# Curtis3340-VCO.net
KiCad netlist of a schematic drawn in EAGLE
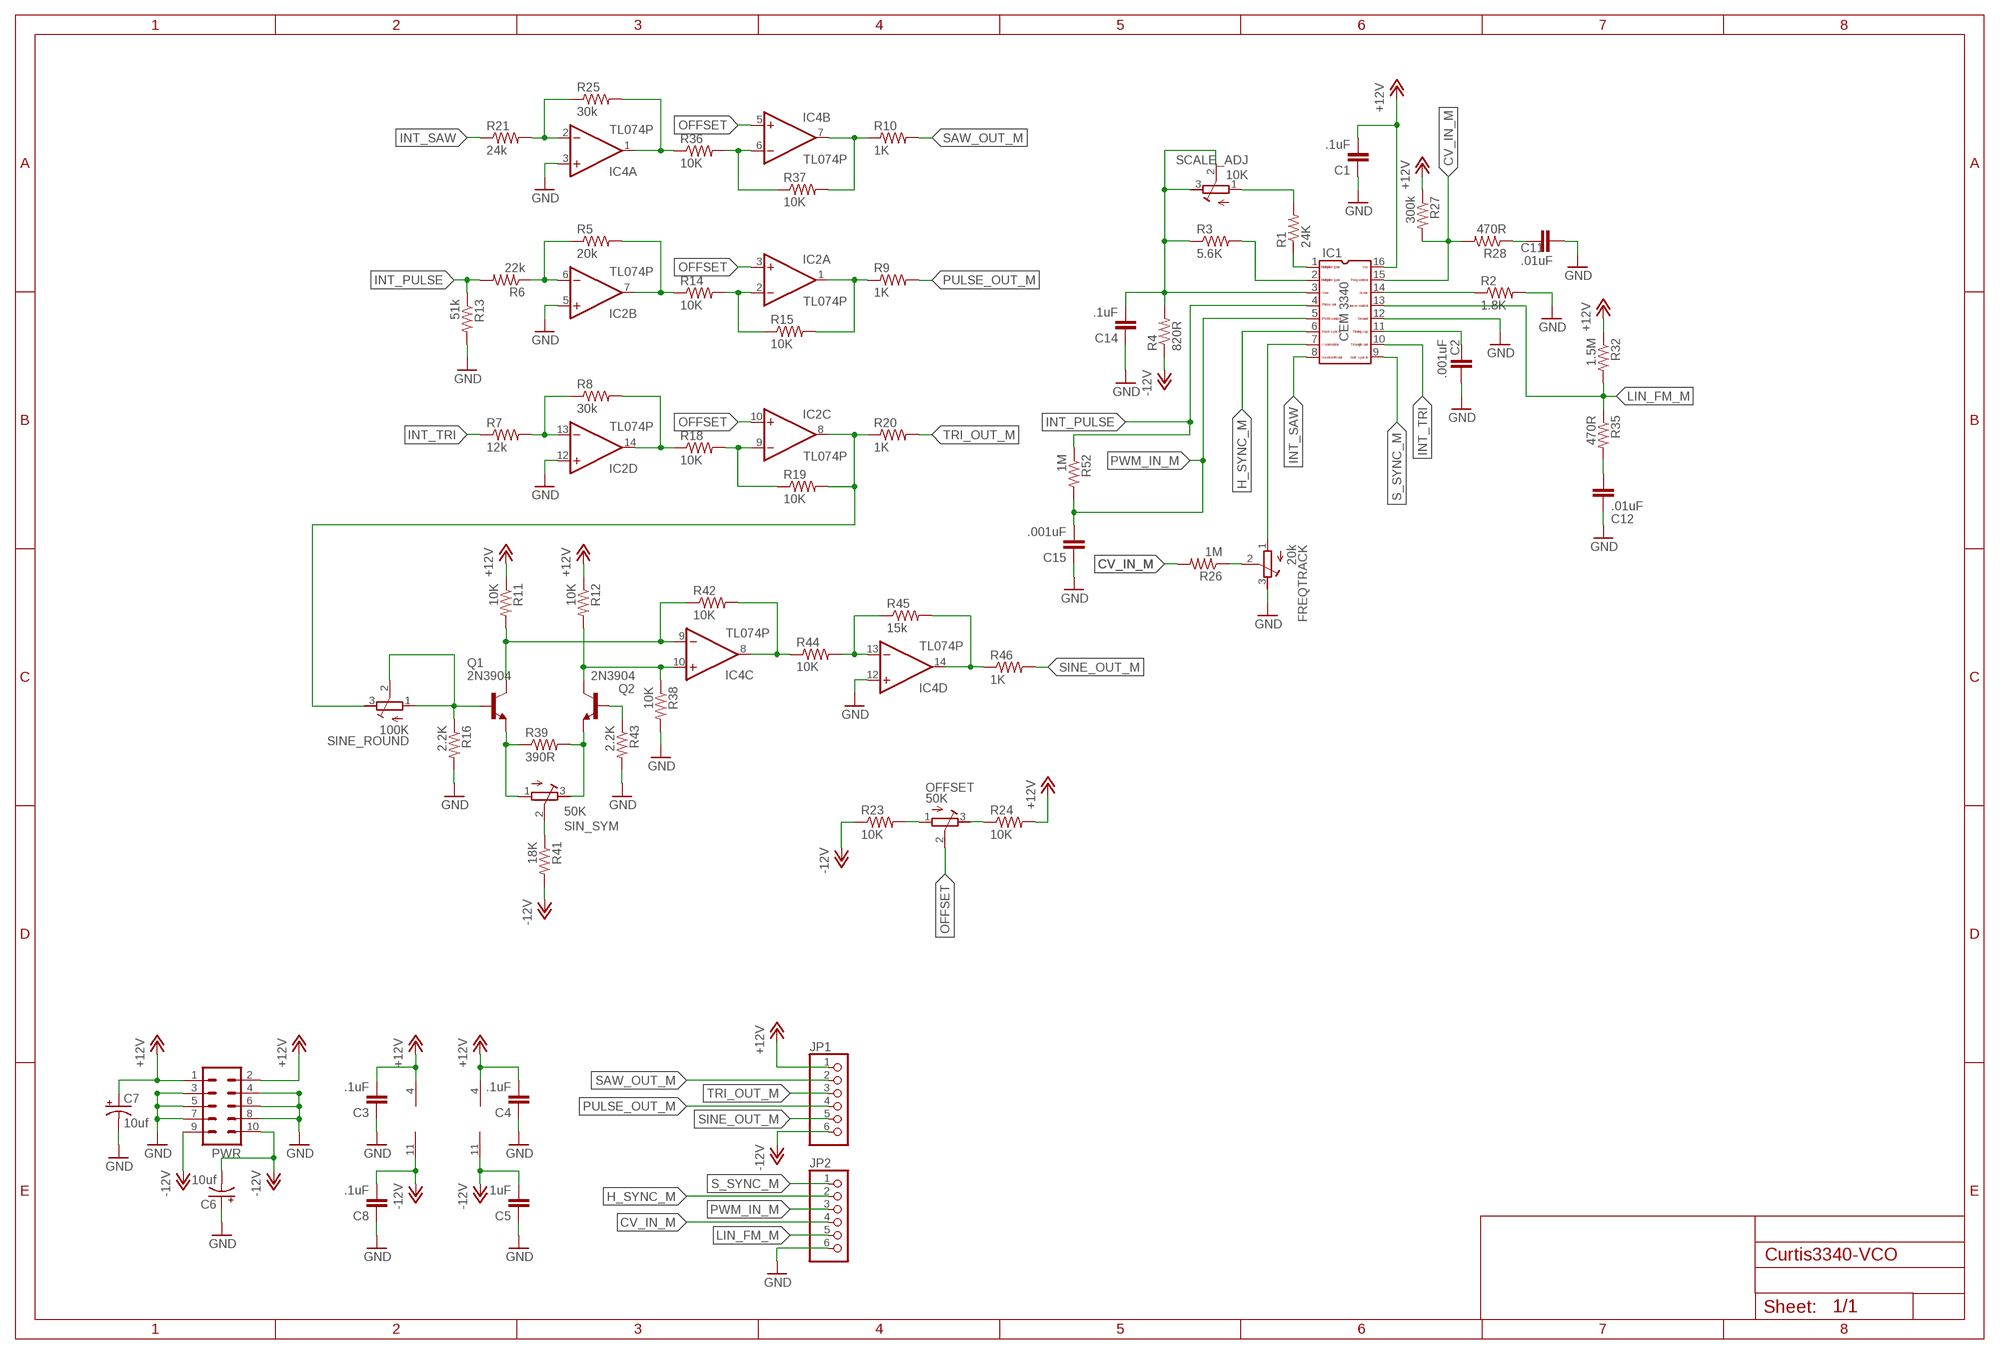
[diagram p0: schematic, sheet 1]

(export (version "E")
  (design (tool "Eeschema 10.0.6"))
  (components
    (comp (ref "C1")
      (value ".1uF")
      (footprint "eagle-import:C050-024X044")
      (libsource (lib "eagle-import") (part "resistor_C-EU050-024X044"))
    )
    (comp (ref "C2")
      (value ".001uF")
      (footprint "eagle-import:C150-054X183")
      (libsource (lib "eagle-import") (part "C-EU150-054X183"))
    )
    (comp (ref "C3")
      (value ".1uF")
      (footprint "eagle-import:C050-024X044")
      (libsource (lib "eagle-import") (part "resistor_C-EU050-024X044"))
    )
    (comp (ref "C4")
      (value ".1uF")
      (footprint "eagle-import:C050-024X044")
      (libsource (lib "eagle-import") (part "resistor_C-EU050-024X044"))
    )
    (comp (ref "C5")
      (value ".1uF")
      (footprint "eagle-import:C050-024X044")
      (libsource (lib "eagle-import") (part "resistor_C-EU050-024X044"))
    )
    (comp (ref "C6")
      (value "10uf")
      (footprint "eagle-import:E2,5-5")
      (libsource (lib "eagle-import") (part "CPOL-USE2.5-5"))
    )
    (comp (ref "C7")
      (value "10uf")
      (footprint "eagle-import:E2,5-5")
      (libsource (lib "eagle-import") (part "CPOL-USE2.5-5"))
    )
    (comp (ref "C8")
      (value ".1uF")
      (footprint "eagle-import:C050-024X044")
      (libsource (lib "eagle-import") (part "resistor_C-EU050-024X044"))
    )
    (comp (ref "C11")
      (value ".01uF")
      (footprint "eagle-import:C050-024X044")
      (libsource (lib "eagle-import") (part "resistor_C-EU050-024X044"))
    )
    (comp (ref "C12")
      (value ".01uF")
      (footprint "eagle-import:C050-024X044")
      (libsource (lib "eagle-import") (part "resistor_C-EU050-024X044"))
    )
    (comp (ref "C14")
      (value ".1uF")
      (footprint "eagle-import:C050-024X044")
      (libsource (lib "eagle-import") (part "resistor_C-EU050-024X044"))
    )
    (comp (ref "C15")
      (value ".001uF")
      (footprint "eagle-import:C050-024X044")
      (libsource (lib "eagle-import") (part "resistor_C-EU050-024X044"))
    )
    (comp (ref "FREQTRACK")
      (value "20k")
      (footprint "eagle-import:RTRIM3296W")
      (libsource (lib "eagle-import") (part "R-TRIMM3296W"))
    )
    (comp (ref "IC1")
      (value "CEM3340")
      (footprint "eagle-import:DIL16")
      (libsource (lib "eagle-import") (part "CEM3340"))
    )
    (comp (ref "IC2")
      (value "TL074P")
      (footprint "eagle-import:DIL14")
      (libsource (lib "eagle-import") (part "TL074P"))
    )
    (comp (ref "IC4")
      (value "TL074P")
      (footprint "eagle-import:DIL14")
      (libsource (lib "eagle-import") (part "linear_262_TL074P"))
    )
    (comp (ref "JP1")
      (value "PINHD-1X6")
      (footprint "eagle-import:1X06")
      (libsource (lib "eagle-import") (part "PINHD-1X6"))
    )
    (comp (ref "JP2")
      (value "PINHD-1X6")
      (footprint "eagle-import:1X06")
      (libsource (lib "eagle-import") (part "PINHD-1X6"))
    )
    (comp (ref "OFFSET")
      (value "50K")
      (footprint "eagle-import:RTRIM3296W")
      (libsource (lib "eagle-import") (part "R-TRIMM3296W"))
    )
    (comp (ref "PWR")
      (value "ML10")
      (footprint "eagle-import:ML10")
      (libsource (lib "eagle-import") (part "ML10"))
    )
    (comp (ref "Q1")
      (value "2N3904")
      (footprint "eagle-import:TO92")
      (libsource (lib "eagle-import") (part "2N3904"))
    )
    (comp (ref "Q2")
      (value "2N3904")
      (footprint "eagle-import:TO92")
      (libsource (lib "eagle-import") (part "2N3904"))
    )
    (comp (ref "R1")
      (value "24K")
      (footprint "eagle-import:0207_7")
      (libsource (lib "eagle-import") (part "R-US_0207/7"))
    )
    (comp (ref "R2")
      (value "1.8K")
      (footprint "eagle-import:0207_7")
      (libsource (lib "eagle-import") (part "R-US_0207/7"))
    )
    (comp (ref "R3")
      (value "5.6K")
      (footprint "eagle-import:0207_7")
      (libsource (lib "eagle-import") (part "R-US_0207/7"))
    )
    (comp (ref "R4")
      (value "820R")
      (footprint "eagle-import:0207_7")
      (libsource (lib "eagle-import") (part "R-US_0207/7"))
    )
    (comp (ref "R5")
      (value "20k")
      (footprint "eagle-import:0207_7")
      (libsource (lib "eagle-import") (part "R-US_0207/7"))
    )
    (comp (ref "R6")
      (value "22k")
      (footprint "eagle-import:0207_7")
      (libsource (lib "eagle-import") (part "R-US_0207/7"))
    )
    (comp (ref "R7")
      (value "12k")
      (footprint "eagle-import:0207_7")
      (libsource (lib "eagle-import") (part "R-US_0207/7"))
    )
    (comp (ref "R8")
      (value "30k")
      (footprint "eagle-import:0207_7")
      (libsource (lib "eagle-import") (part "R-US_0207/7"))
    )
    (comp (ref "R9")
      (value "1K")
      (footprint "eagle-import:0207_7")
      (libsource (lib "eagle-import") (part "R-US_0207/7"))
    )
    (comp (ref "R10")
      (value "1K")
      (footprint "eagle-import:0207_7")
      (libsource (lib "eagle-import") (part "R-US_0207/7"))
    )
    (comp (ref "R11")
      (value "10K")
      (footprint "eagle-import:0207_7")
      (libsource (lib "eagle-import") (part "R-US_0207/7"))
    )
    (comp (ref "R12")
      (value "10K")
      (footprint "eagle-import:0207_7")
      (libsource (lib "eagle-import") (part "R-US_0207/7"))
    )
    (comp (ref "R13")
      (value "51k")
      (footprint "eagle-import:0207_7")
      (libsource (lib "eagle-import") (part "R-US_0207/7"))
    )
    (comp (ref "R14")
      (value "10K")
      (footprint "eagle-import:0207_7")
      (libsource (lib "eagle-import") (part "R-US_0207/7"))
    )
    (comp (ref "R15")
      (value "10K")
      (footprint "eagle-import:0207_7")
      (libsource (lib "eagle-import") (part "R-US_0207/7"))
    )
    (comp (ref "R16")
      (value "2.2K")
      (footprint "eagle-import:0207_7")
      (libsource (lib "eagle-import") (part "R-US_0207/7"))
    )
    (comp (ref "R18")
      (value "10K")
      (footprint "eagle-import:0207_7")
      (libsource (lib "eagle-import") (part "R-US_0207/7"))
    )
    (comp (ref "R19")
      (value "10K")
      (footprint "eagle-import:0207_7")
      (libsource (lib "eagle-import") (part "R-US_0207/7"))
    )
    (comp (ref "R20")
      (value "1K")
      (footprint "eagle-import:0207_7")
      (libsource (lib "eagle-import") (part "R-US_0207/7"))
    )
    (comp (ref "R21")
      (value "24k")
      (footprint "eagle-import:0207_7")
      (libsource (lib "eagle-import") (part "R-US_0207/7"))
    )
    (comp (ref "R23")
      (value "10K")
      (footprint "eagle-import:0207_7")
      (libsource (lib "eagle-import") (part "R-US_0207/7"))
    )
    (comp (ref "R24")
      (value "10K")
      (footprint "eagle-import:0207_7")
      (libsource (lib "eagle-import") (part "resistor_348_R-US_0207/7"))
    )
    (comp (ref "R25")
      (value "30k")
      (footprint "eagle-import:0207_7")
      (libsource (lib "eagle-import") (part "R-US_0207/7"))
    )
    (comp (ref "R26")
      (value "1M")
      (footprint "eagle-import:0207_7")
      (libsource (lib "eagle-import") (part "R-US_0207/7"))
    )
    (comp (ref "R27")
      (value "300k")
      (footprint "eagle-import:0207_7")
      (libsource (lib "eagle-import") (part "R-US_0207/7"))
    )
    (comp (ref "R28")
      (value "470R")
      (footprint "eagle-import:0207_7")
      (libsource (lib "eagle-import") (part "R-US_0207/7"))
    )
    (comp (ref "R32")
      (value "1.5M")
      (footprint "eagle-import:0207_7")
      (libsource (lib "eagle-import") (part "R-US_0207/7"))
    )
    (comp (ref "R35")
      (value "470R")
      (footprint "eagle-import:0207_7")
      (libsource (lib "eagle-import") (part "R-US_0207/7"))
    )
    (comp (ref "R36")
      (value "10K")
      (footprint "eagle-import:0207_7")
      (libsource (lib "eagle-import") (part "R-US_0207/7"))
    )
    (comp (ref "R37")
      (value "10K")
      (footprint "eagle-import:0207_7")
      (libsource (lib "eagle-import") (part "R-US_0207/7"))
    )
    (comp (ref "R38")
      (value "10K")
      (footprint "eagle-import:0207_7")
      (libsource (lib "eagle-import") (part "R-US_0207/7"))
    )
    (comp (ref "R39")
      (value "390R")
      (footprint "eagle-import:0207_7")
      (libsource (lib "eagle-import") (part "R-US_0207/7"))
    )
    (comp (ref "R41")
      (value "18K")
      (footprint "eagle-import:0207_7")
      (libsource (lib "eagle-import") (part "R-US_0207/7"))
    )
    (comp (ref "R42")
      (value "10K")
      (footprint "eagle-import:0207_7")
      (libsource (lib "eagle-import") (part "R-US_0207/7"))
    )
    (comp (ref "R43")
      (value "2.2K")
      (footprint "eagle-import:0207_7")
      (libsource (lib "eagle-import") (part "R-US_0207/7"))
    )
    (comp (ref "R44")
      (value "10K")
      (footprint "eagle-import:0207_7")
      (libsource (lib "eagle-import") (part "R-US_0207/7"))
    )
    (comp (ref "R45")
      (value "15k")
      (footprint "eagle-import:0207_7")
      (libsource (lib "eagle-import") (part "R-US_0207/7"))
    )
    (comp (ref "R46")
      (value "1K")
      (footprint "eagle-import:0207_7")
      (libsource (lib "eagle-import") (part "R-US_0207/7"))
    )
    (comp (ref "R52")
      (value "1M")
      (footprint "eagle-import:0207_7")
      (libsource (lib "eagle-import") (part "R-US_0207/7"))
    )
    (comp (ref "SCALE_ADJ")
      (value "10K")
      (footprint "eagle-import:RTRIM3296W")
      (libsource (lib "eagle-import") (part "R-TRIMM3296W"))
    )
    (comp (ref "SINE_ROUND")
      (value "100K")
      (footprint "eagle-import:RTRIM3296W")
      (libsource (lib "eagle-import") (part "R-TRIMM3296W"))
    )
    (comp (ref "SIN_SYM")
      (value "50K")
      (footprint "eagle-import:RTRIM3296W")
      (libsource (lib "eagle-import") (part "R-TRIMM3296W"))
    )
  )
  (nets
    (net (code "1") (name "+12V") (class "Default")
      (node (ref "C1") (pin "2") (pinfunction "2_2") (pintype "passive"))
      (node (ref "C3") (pin "2") (pinfunction "2_2") (pintype "passive"))
      (node (ref "C4") (pin "2") (pinfunction "2_2") (pintype "passive"))
      (node (ref "C7") (pin "+") (pinfunction "+_+") (pintype "passive"))
      (node (ref "IC1") (pin "16") (pinfunction "16_16") (pintype "power_in"))
      (node (ref "IC2") (pin "4") (pinfunction "V+_4") (pintype "power_in"))
      (node (ref "IC4") (pin "4") (pinfunction "V+_4") (pintype "power_in"))
      (node (ref "JP1") (pin "1") (pinfunction "1_1") (pintype "passive"))
      (node (ref "PWR") (pin "1") (pinfunction "1_1") (pintype "passive"))
      (node (ref "PWR") (pin "2") (pinfunction "2_2") (pintype "passive"))
      (node (ref "R11") (pin "1") (pinfunction "1_1") (pintype "passive"))
      (node (ref "R12") (pin "1") (pinfunction "1_1") (pintype "passive"))
      (node (ref "R24") (pin "2") (pinfunction "2_2") (pintype "passive"))
      (node (ref "R27") (pin "1") (pinfunction "1_1") (pintype "passive"))
      (node (ref "R32") (pin "1") (pinfunction "1_1") (pintype "passive"))
    )
    (net (code "2") (name "-12V") (class "Default")
      (node (ref "C5") (pin "2") (pinfunction "2_2") (pintype "passive"))
      (node (ref "C6") (pin "-") (pinfunction "-_-") (pintype "passive"))
      (node (ref "C8") (pin "2") (pinfunction "2_2") (pintype "passive"))
      (node (ref "IC2") (pin "11") (pinfunction "V-_11") (pintype "power_in"))
      (node (ref "IC4") (pin "11") (pinfunction "V-_11") (pintype "power_in"))
      (node (ref "JP1") (pin "6") (pinfunction "6_6") (pintype "passive"))
      (node (ref "PWR") (pin "10") (pinfunction "10_10") (pintype "passive"))
      (node (ref "PWR") (pin "9") (pinfunction "9_9") (pintype "passive"))
      (node (ref "R23") (pin "1") (pinfunction "1_1") (pintype "passive"))
      (node (ref "R4") (pin "1") (pinfunction "1_1") (pintype "passive"))
      (node (ref "R41") (pin "2") (pinfunction "2_2") (pintype "passive"))
    )
    (net (code "3") (name "CV_IN_M") (class "Default")
      (node (ref "IC1") (pin "15") (pinfunction "15_15") (pintype "input"))
      (node (ref "JP2") (pin "4") (pinfunction "4_4") (pintype "passive"))
      (node (ref "R26") (pin "2") (pinfunction "2_2") (pintype "passive"))
      (node (ref "R27") (pin "2") (pinfunction "2_2") (pintype "passive"))
      (node (ref "R28") (pin "2") (pinfunction "2_2") (pintype "passive"))
    )
    (net (code "4") (name "GND") (class "Default")
      (node (ref "C1") (pin "1") (pinfunction "1_1") (pintype "passive"))
      (node (ref "C11") (pin "1") (pinfunction "1_1") (pintype "passive"))
      (node (ref "C12") (pin "2") (pinfunction "2_2") (pintype "passive"))
      (node (ref "C14") (pin "1") (pinfunction "1_1") (pintype "passive"))
      (node (ref "C15") (pin "1") (pinfunction "1_1") (pintype "passive"))
      (node (ref "C2") (pin "2") (pinfunction "2_2") (pintype "passive"))
      (node (ref "C3") (pin "1") (pinfunction "1_1") (pintype "passive"))
      (node (ref "C4") (pin "1") (pinfunction "1_1") (pintype "passive"))
      (node (ref "C5") (pin "1") (pinfunction "1_1") (pintype "passive"))
      (node (ref "C6") (pin "+") (pinfunction "+_+") (pintype "passive"))
      (node (ref "C7") (pin "-") (pinfunction "-_-") (pintype "passive"))
      (node (ref "C8") (pin "1") (pinfunction "1_1") (pintype "passive"))
      (node (ref "FREQTRACK") (pin "3") (pinfunction "E_3") (pintype "passive"))
      (node (ref "IC1") (pin "12") (pinfunction "12_12") (pintype "power_in"))
      (node (ref "IC2") (pin "12") (pinfunction "+IN_12") (pintype "input"))
      (node (ref "IC2") (pin "5") (pinfunction "+IN_5") (pintype "input"))
      (node (ref "IC4") (pin "12") (pinfunction "+IN_12") (pintype "input"))
      (node (ref "IC4") (pin "3") (pinfunction "+IN_3") (pintype "input"))
      (node (ref "JP2") (pin "6") (pinfunction "6_6") (pintype "passive"))
      (node (ref "PWR") (pin "3") (pinfunction "3_3") (pintype "passive"))
      (node (ref "PWR") (pin "4") (pinfunction "4_4") (pintype "passive"))
      (node (ref "PWR") (pin "5") (pinfunction "5_5") (pintype "passive"))
      (node (ref "PWR") (pin "6") (pinfunction "6_6") (pintype "passive"))
      (node (ref "PWR") (pin "7") (pinfunction "7_7") (pintype "passive"))
      (node (ref "PWR") (pin "8") (pinfunction "8_8") (pintype "passive"))
      (node (ref "R13") (pin "2") (pinfunction "2_2") (pintype "passive"))
      (node (ref "R16") (pin "2") (pinfunction "2_2") (pintype "passive"))
      (node (ref "R2") (pin "2") (pinfunction "2_2") (pintype "passive"))
      (node (ref "R38") (pin "2") (pinfunction "2_2") (pintype "passive"))
      (node (ref "R43") (pin "2") (pinfunction "2_2") (pintype "passive"))
    )
    (net (code "5") (name "H_SYNC_M") (class "Default")
      (node (ref "IC1") (pin "6") (pinfunction "6_6") (pintype "input"))
      (node (ref "JP2") (pin "2") (pinfunction "2_2") (pintype "passive"))
    )
    (net (code "6") (name "INT_PULSE") (class "Default")
      (node (ref "IC1") (pin "4") (pinfunction "4_4") (pintype "output"))
      (node (ref "R13") (pin "1") (pinfunction "1_1") (pintype "passive"))
      (node (ref "R52") (pin "1") (pinfunction "1_1") (pintype "passive"))
      (node (ref "R6") (pin "2") (pinfunction "2_2") (pintype "passive"))
    )
    (net (code "7") (name "INT_SAW") (class "Default")
      (node (ref "IC1") (pin "8") (pinfunction "8_8") (pintype "output"))
      (node (ref "R21") (pin "1") (pinfunction "1_1") (pintype "passive"))
    )
    (net (code "8") (name "INT_TRI") (class "Default")
      (node (ref "IC1") (pin "10") (pinfunction "10_10") (pintype "output"))
      (node (ref "R7") (pin "1") (pinfunction "1_1") (pintype "passive"))
    )
    (net (code "9") (name "LIN_FM_M") (class "Default")
      (node (ref "IC1") (pin "13") (pinfunction "13_13") (pintype "input"))
      (node (ref "JP2") (pin "5") (pinfunction "5_5") (pintype "passive"))
      (node (ref "R32") (pin "2") (pinfunction "2_2") (pintype "passive"))
      (node (ref "R35") (pin "1") (pinfunction "1_1") (pintype "passive"))
    )
    (net (code "10") (name "Net-(C2-Pad1)") (class "Default")
      (node (ref "C2") (pin "1") (pinfunction "1_1") (pintype "passive"))
      (node (ref "IC1") (pin "11") (pinfunction "11_11") (pintype "bidirectional"))
    )
    (net (code "11") (name "Net-(C11-Pad2)") (class "Default")
      (node (ref "C11") (pin "2") (pinfunction "2_2") (pintype "passive"))
      (node (ref "R28") (pin "1") (pinfunction "1_1") (pintype "passive"))
    )
    (net (code "12") (name "Net-(C12-Pad1)") (class "Default")
      (node (ref "C12") (pin "1") (pinfunction "1_1") (pintype "passive"))
      (node (ref "R35") (pin "2") (pinfunction "2_2") (pintype "passive"))
    )
    (net (code "13") (name "Net-(FREQTRACK-A)") (class "Default")
      (node (ref "FREQTRACK") (pin "1") (pinfunction "A_1") (pintype "passive"))
      (node (ref "IC1") (pin "7") (pinfunction "7_7") (pintype "bidirectional"))
    )
    (net (code "14") (name "Net-(FREQTRACK-S)") (class "Default")
      (node (ref "FREQTRACK") (pin "2") (pinfunction "S_2") (pintype "passive"))
      (node (ref "R26") (pin "1") (pinfunction "1_1") (pintype "passive"))
    )
    (net (code "15") (name "Net-(IC1-Pad1)") (class "Default")
      (node (ref "IC1") (pin "1") (pinfunction "1_1") (pintype "bidirectional"))
      (node (ref "R1") (pin "1") (pinfunction "1_1") (pintype "passive"))
    )
    (net (code "16") (name "Net-(IC1-Pad2)") (class "Default")
      (node (ref "IC1") (pin "2") (pinfunction "2_2") (pintype "bidirectional"))
      (node (ref "R3") (pin "2") (pinfunction "2_2") (pintype "passive"))
    )
    (net (code "17") (name "Net-(IC1-Pad14)") (class "Default")
      (node (ref "IC1") (pin "14") (pinfunction "14_14") (pintype "input"))
      (node (ref "R2") (pin "1") (pinfunction "1_1") (pintype "passive"))
    )
    (net (code "18") (name "Net-(IC2A--IN)") (class "Default")
      (node (ref "IC2") (pin "2") (pinfunction "-IN_2") (pintype "input"))
      (node (ref "R14") (pin "2") (pinfunction "2_2") (pintype "passive"))
      (node (ref "R15") (pin "1") (pinfunction "1_1") (pintype "passive"))
    )
    (net (code "19") (name "Net-(IC2A-OUT)") (class "Default")
      (node (ref "IC2") (pin "1") (pinfunction "OUT_1") (pintype "output"))
      (node (ref "R15") (pin "2") (pinfunction "2_2") (pintype "passive"))
      (node (ref "R9") (pin "1") (pinfunction "1_1") (pintype "passive"))
    )
    (net (code "20") (name "Net-(IC2B--IN)") (class "Default")
      (node (ref "IC2") (pin "6") (pinfunction "-IN_6") (pintype "input"))
      (node (ref "R5") (pin "1") (pinfunction "1_1") (pintype "passive"))
      (node (ref "R6") (pin "1") (pinfunction "1_1") (pintype "passive"))
    )
    (net (code "21") (name "Net-(IC2B-OUT)") (class "Default")
      (node (ref "IC2") (pin "7") (pinfunction "OUT_7") (pintype "output"))
      (node (ref "R14") (pin "1") (pinfunction "1_1") (pintype "passive"))
      (node (ref "R5") (pin "2") (pinfunction "2_2") (pintype "passive"))
    )
    (net (code "22") (name "Net-(IC2C--IN)") (class "Default")
      (node (ref "IC2") (pin "9") (pinfunction "-IN_9") (pintype "input"))
      (node (ref "R18") (pin "2") (pinfunction "2_2") (pintype "passive"))
      (node (ref "R19") (pin "1") (pinfunction "1_1") (pintype "passive"))
    )
    (net (code "23") (name "Net-(IC2C-OUT)") (class "Default")
      (node (ref "IC2") (pin "8") (pinfunction "OUT_8") (pintype "output"))
      (node (ref "R19") (pin "2") (pinfunction "2_2") (pintype "passive"))
      (node (ref "R20") (pin "1") (pinfunction "1_1") (pintype "passive"))
      (node (ref "SINE_ROUND") (pin "3") (pinfunction "E_3") (pintype "passive"))
    )
    (net (code "24") (name "Net-(IC2D--IN)") (class "Default")
      (node (ref "IC2") (pin "13") (pinfunction "-IN_13") (pintype "input"))
      (node (ref "R7") (pin "2") (pinfunction "2_2") (pintype "passive"))
      (node (ref "R8") (pin "1") (pinfunction "1_1") (pintype "passive"))
    )
    (net (code "25") (name "Net-(IC2D-OUT)") (class "Default")
      (node (ref "IC2") (pin "14") (pinfunction "OUT_14") (pintype "output"))
      (node (ref "R18") (pin "1") (pinfunction "1_1") (pintype "passive"))
      (node (ref "R8") (pin "2") (pinfunction "2_2") (pintype "passive"))
    )
    (net (code "26") (name "Net-(IC4A--IN)") (class "Default")
      (node (ref "IC4") (pin "2") (pinfunction "-IN_2") (pintype "input"))
      (node (ref "R21") (pin "2") (pinfunction "2_2") (pintype "passive"))
      (node (ref "R25") (pin "1") (pinfunction "1_1") (pintype "passive"))
    )
    (net (code "27") (name "Net-(IC4A-OUT)") (class "Default")
      (node (ref "IC4") (pin "1") (pinfunction "OUT_1") (pintype "output"))
      (node (ref "R25") (pin "2") (pinfunction "2_2") (pintype "passive"))
      (node (ref "R36") (pin "1") (pinfunction "1_1") (pintype "passive"))
    )
    (net (code "28") (name "Net-(IC4B--IN)") (class "Default")
      (node (ref "IC4") (pin "6") (pinfunction "-IN_6") (pintype "input"))
      (node (ref "R36") (pin "2") (pinfunction "2_2") (pintype "passive"))
      (node (ref "R37") (pin "1") (pinfunction "1_1") (pintype "passive"))
    )
    (net (code "29") (name "Net-(IC4B-OUT)") (class "Default")
      (node (ref "IC4") (pin "7") (pinfunction "OUT_7") (pintype "output"))
      (node (ref "R10") (pin "1") (pinfunction "1_1") (pintype "passive"))
      (node (ref "R37") (pin "2") (pinfunction "2_2") (pintype "passive"))
    )
    (net (code "30") (name "Net-(IC4C-+IN)") (class "Default")
      (node (ref "IC4") (pin "10") (pinfunction "+IN_10") (pintype "input"))
      (node (ref "Q2") (pin "1") (pinfunction "C_1") (pintype "passive"))
      (node (ref "R12") (pin "2") (pinfunction "2_2") (pintype "passive"))
      (node (ref "R38") (pin "1") (pinfunction "1_1") (pintype "passive"))
    )
    (net (code "31") (name "Net-(IC4C--IN)") (class "Default")
      (node (ref "IC4") (pin "9") (pinfunction "-IN_9") (pintype "input"))
      (node (ref "Q1") (pin "1") (pinfunction "C_1") (pintype "passive"))
      (node (ref "R11") (pin "2") (pinfunction "2_2") (pintype "passive"))
      (node (ref "R42") (pin "1") (pinfunction "1_1") (pintype "passive"))
    )
    (net (code "32") (name "Net-(IC4C-OUT)") (class "Default")
      (node (ref "IC4") (pin "8") (pinfunction "OUT_8") (pintype "output"))
      (node (ref "R42") (pin "2") (pinfunction "2_2") (pintype "passive"))
      (node (ref "R44") (pin "1") (pinfunction "1_1") (pintype "passive"))
    )
    (net (code "33") (name "Net-(IC4D--IN)") (class "Default")
      (node (ref "IC4") (pin "13") (pinfunction "-IN_13") (pintype "input"))
      (node (ref "R44") (pin "2") (pinfunction "2_2") (pintype "passive"))
      (node (ref "R45") (pin "1") (pinfunction "1_1") (pintype "passive"))
    )
    (net (code "34") (name "Net-(IC4D-OUT)") (class "Default")
      (node (ref "IC4") (pin "14") (pinfunction "OUT_14") (pintype "output"))
      (node (ref "R45") (pin "2") (pinfunction "2_2") (pintype "passive"))
      (node (ref "R46") (pin "1") (pinfunction "1_1") (pintype "passive"))
    )
    (net (code "35") (name "Net-(OFFSET-A)") (class "Default")
      (node (ref "OFFSET") (pin "1") (pinfunction "A_1") (pintype "passive"))
      (node (ref "R23") (pin "2") (pinfunction "2_2") (pintype "passive"))
    )
    (net (code "36") (name "Net-(OFFSET-E)") (class "Default")
      (node (ref "OFFSET") (pin "3") (pinfunction "E_3") (pintype "passive"))
      (node (ref "R24") (pin "1") (pinfunction "1_1") (pintype "passive"))
    )
    (net (code "37") (name "Net-(Q1-B)") (class "Default")
      (node (ref "Q1") (pin "2") (pinfunction "B_2") (pintype "passive"))
      (node (ref "R16") (pin "1") (pinfunction "1_1") (pintype "passive"))
      (node (ref "SINE_ROUND") (pin "1") (pinfunction "A_1") (pintype "passive"))
      (node (ref "SINE_ROUND") (pin "2") (pinfunction "S_2") (pintype "passive"))
    )
    (net (code "38") (name "Net-(Q1-E)") (class "Default")
      (node (ref "Q1") (pin "3") (pinfunction "E_3") (pintype "passive"))
      (node (ref "R39") (pin "1") (pinfunction "1_1") (pintype "passive"))
      (node (ref "SIN_SYM") (pin "1") (pinfunction "A_1") (pintype "passive"))
    )
    (net (code "39") (name "Net-(Q2-B)") (class "Default")
      (node (ref "Q2") (pin "2") (pinfunction "B_2") (pintype "passive"))
      (node (ref "R43") (pin "1") (pinfunction "1_1") (pintype "passive"))
    )
    (net (code "40") (name "Net-(Q2-E)") (class "Default")
      (node (ref "Q2") (pin "3") (pinfunction "E_3") (pintype "passive"))
      (node (ref "R39") (pin "2") (pinfunction "2_2") (pintype "passive"))
      (node (ref "SIN_SYM") (pin "3") (pinfunction "E_3") (pintype "passive"))
    )
    (net (code "41") (name "Net-(SCALE_ADJ-A)") (class "Default")
      (node (ref "R1") (pin "2") (pinfunction "2_2") (pintype "passive"))
      (node (ref "SCALE_ADJ") (pin "1") (pinfunction "A_1") (pintype "passive"))
    )
    (net (code "42") (name "Net-(SCALE_ADJ-E)") (class "Default")
      (node (ref "C14") (pin "2") (pinfunction "2_2") (pintype "passive"))
      (node (ref "IC1") (pin "3") (pinfunction "3_3") (pintype "power_in"))
      (node (ref "R3") (pin "1") (pinfunction "1_1") (pintype "passive"))
      (node (ref "R4") (pin "2") (pinfunction "2_2") (pintype "passive"))
      (node (ref "SCALE_ADJ") (pin "2") (pinfunction "S_2") (pintype "passive"))
      (node (ref "SCALE_ADJ") (pin "3") (pinfunction "E_3") (pintype "passive"))
    )
    (net (code "43") (name "Net-(SIN_SYM-S)") (class "Default")
      (node (ref "R41") (pin "1") (pinfunction "1_1") (pintype "passive"))
      (node (ref "SIN_SYM") (pin "2") (pinfunction "S_2") (pintype "passive"))
    )
    (net (code "44") (name "OFFSET") (class "Default")
      (node (ref "IC2") (pin "10") (pinfunction "+IN_10") (pintype "input"))
      (node (ref "IC2") (pin "3") (pinfunction "+IN_3") (pintype "input"))
      (node (ref "IC4") (pin "5") (pinfunction "+IN_5") (pintype "input"))
      (node (ref "OFFSET") (pin "2") (pinfunction "S_2") (pintype "passive"))
    )
    (net (code "45") (name "PULSE_OUT_M") (class "Default")
      (node (ref "JP1") (pin "4") (pinfunction "4_4") (pintype "passive"))
      (node (ref "R9") (pin "2") (pinfunction "2_2") (pintype "passive"))
    )
    (net (code "46") (name "PWM_IN_M") (class "Default")
      (node (ref "C15") (pin "2") (pinfunction "2_2") (pintype "passive"))
      (node (ref "IC1") (pin "5") (pinfunction "5_5") (pintype "input"))
      (node (ref "JP2") (pin "3") (pinfunction "3_3") (pintype "passive"))
      (node (ref "R52") (pin "2") (pinfunction "2_2") (pintype "passive"))
    )
    (net (code "47") (name "SAW_OUT_M") (class "Default")
      (node (ref "JP1") (pin "2") (pinfunction "2_2") (pintype "passive"))
      (node (ref "R10") (pin "2") (pinfunction "2_2") (pintype "passive"))
    )
    (net (code "48") (name "SINE_OUT_M") (class "Default")
      (node (ref "JP1") (pin "5") (pinfunction "5_5") (pintype "passive"))
      (node (ref "R46") (pin "2") (pinfunction "2_2") (pintype "passive"))
    )
    (net (code "49") (name "S_SYNC_M") (class "Default")
      (node (ref "IC1") (pin "9") (pinfunction "9_9") (pintype "input"))
      (node (ref "JP2") (pin "1") (pinfunction "1_1") (pintype "passive"))
    )
    (net (code "50") (name "TRI_OUT_M") (class "Default")
      (node (ref "JP1") (pin "3") (pinfunction "3_3") (pintype "passive"))
      (node (ref "R20") (pin "2") (pinfunction "2_2") (pintype "passive"))
    )
  )
)
